# BLDC-FTDI.net
KiCad netlist of a schematic drawn in Altium Designer
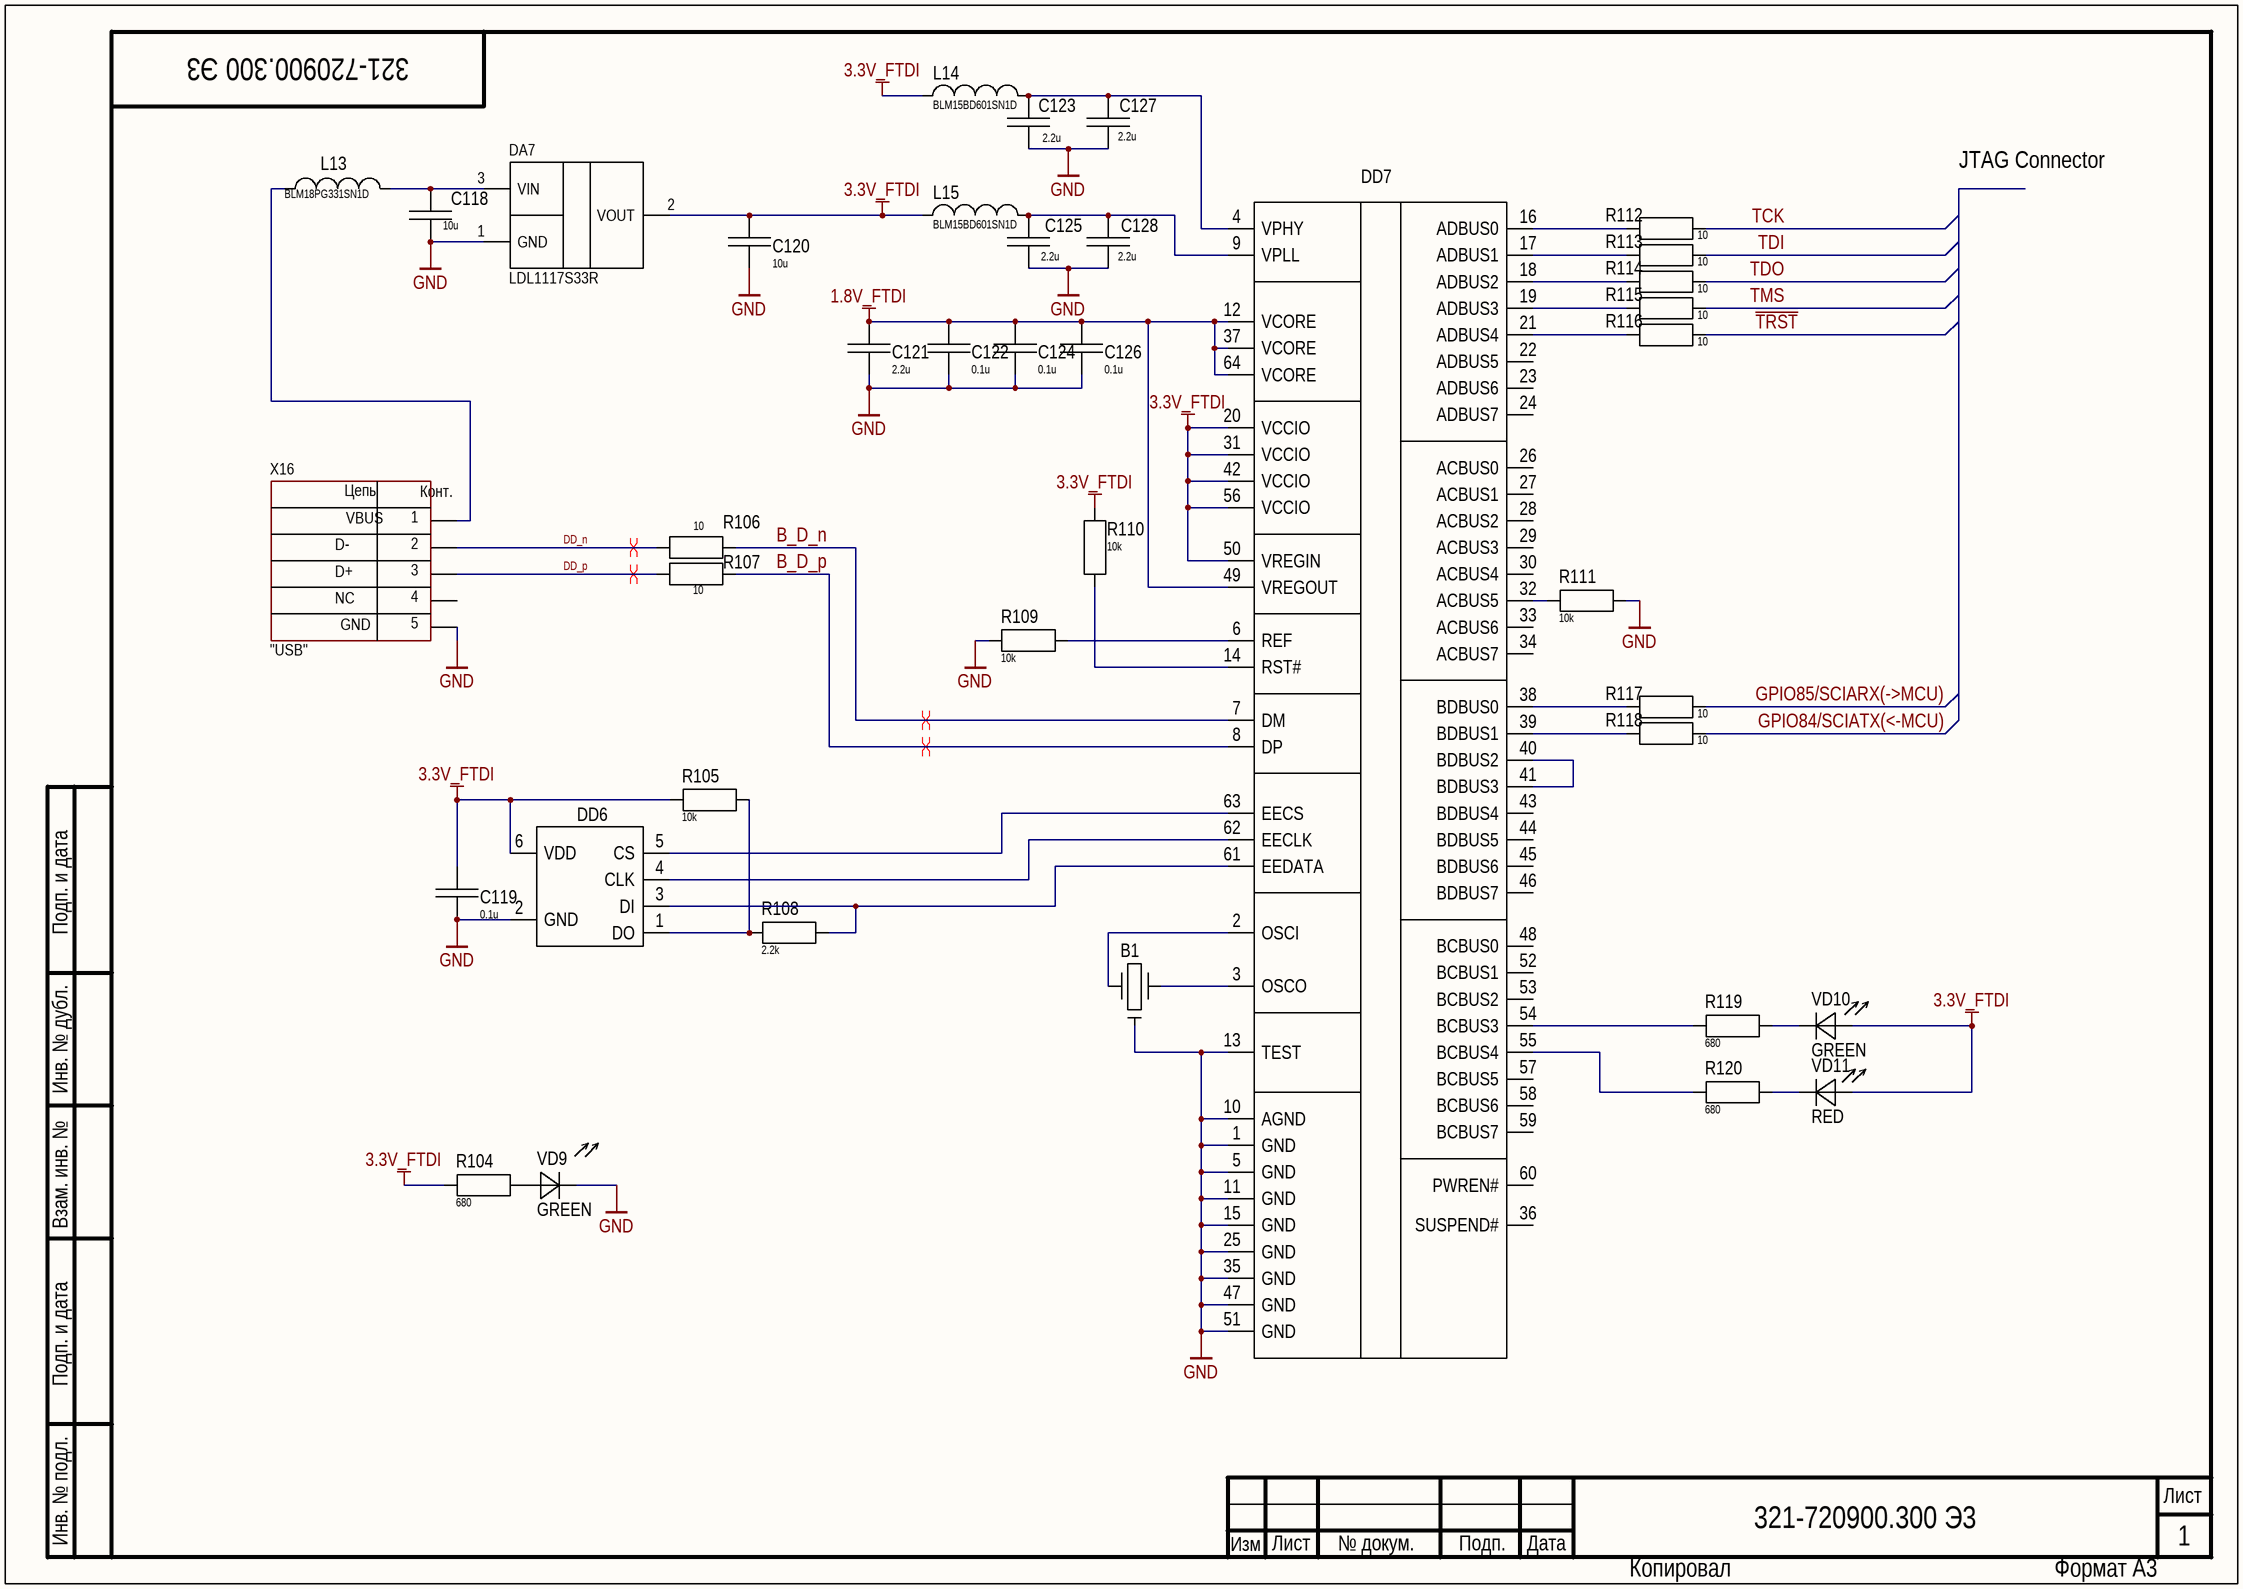
[diagram p0: BLDC-FTDI.SchDoc]

(export (version "E")
  (design (tool "Eeschema 10.0.6"))
  (components
    (comp (ref "B1")
      (value "CSTCE12M0G52-R0")
      (footprint "OSC: CSTCE")
      (libsource (lib "BKM_SCH_Lib") (part "CSTCE12M0G52-R0"))
    )
    (comp (ref "C118")
      (value "10u")
      (footprint "CAP: 0805")
      (fields (field (name "VOLTAGE") "6.3V") (field (name "PARTNUMBER") "CC0402MRX5R5BB106"))
      (libsource (lib "Fider_Board_Lib") (part "CAP 0805"))
    )
    (comp (ref "C119")
      (value "0.1u")
      (footprint "CAP: 0402")
      (fields
        (field (name "VOLTAGE") "10V")
        (field (name "PARTNUMBER") "C0402C104K8PAC")
        (field (name "MANUFACTURER") "Kemet")
      )
      (libsource (lib "Fider_Board_Lib") (part "CAP 0402"))
    )
    (comp (ref "C120")
      (value "10u")
      (footprint "CAP: 0805")
      (fields (field (name "VOLTAGE") "6.3V") (field (name "PARTNUMBER") "CC0402MRX5R5BB106"))
      (libsource (lib "Fider_Board_Lib") (part "CAP 0805"))
    )
    (comp (ref "C121")
      (value "2.2u")
      (footprint "CAP: 0402")
      (fields (field (name "VOLTAGE") "6.3V") (field (name "PARTNUMBER") "CC0402MRX5R5BB106"))
      (libsource (lib "Fider_Board_Lib") (part "CAP 0402"))
    )
    (comp (ref "C122")
      (value "0.1u")
      (footprint "CAP: 0402")
      (fields
        (field (name "VOLTAGE") "10V")
        (field (name "PARTNUMBER") "C0402C104K8PAC")
        (field (name "MANUFACTURER") "Kemet")
      )
      (libsource (lib "Fider_Board_Lib") (part "CAP 0402"))
    )
    (comp (ref "C123")
      (value "2.2u")
      (footprint "CAP: 0402")
      (fields (field (name "VOLTAGE") "6.3V") (field (name "PARTNUMBER") "CC0402MRX5R5BB106"))
      (libsource (lib "Fider_Board_Lib") (part "CAP 0402"))
    )
    (comp (ref "C124")
      (value "0.1u")
      (footprint "CAP: 0402")
      (fields
        (field (name "VOLTAGE") "10V")
        (field (name "PARTNUMBER") "C0402C104K8PAC")
        (field (name "MANUFACTURER") "Kemet")
      )
      (libsource (lib "Fider_Board_Lib") (part "CAP 0402"))
    )
    (comp (ref "C125")
      (value "2.2u")
      (footprint "CAP: 0402")
      (fields (field (name "VOLTAGE") "6.3V") (field (name "PARTNUMBER") "CC0402MRX5R5BB106"))
      (libsource (lib "Fider_Board_Lib") (part "CAP 0402"))
    )
    (comp (ref "C126")
      (value "0.1u")
      (footprint "CAP: 0402")
      (fields
        (field (name "VOLTAGE") "10V")
        (field (name "PARTNUMBER") "C0402C104K8PAC")
        (field (name "MANUFACTURER") "Kemet")
      )
      (libsource (lib "Fider_Board_Lib") (part "CAP 0402"))
    )
    (comp (ref "C127")
      (value "2.2u")
      (footprint "CAP: 0402")
      (fields (field (name "VOLTAGE") "6.3V") (field (name "PARTNUMBER") "CC0402MRX5R5BB106"))
      (libsource (lib "Fider_Board_Lib") (part "CAP 0402"))
    )
    (comp (ref "C128")
      (value "2.2u")
      (footprint "CAP: 0402")
      (fields (field (name "VOLTAGE") "6.3V") (field (name "PARTNUMBER") "CC0402MRX5R5BB106"))
      (libsource (lib "Fider_Board_Lib") (part "CAP 0402"))
    )
    (comp (ref "DA7")
      (value "~")
      (footprint "StandardCase:SOT223")
      (description "Linear voltage regulator")
      (fields
        (field (name "MANUFACTURER") "STMicroelectronics")
        (field (name "VALUEMANUFACTURERPARTNUMBER") "Linear voltage regulator, input 3.9...18V, 0.6V, output 3.3V, 1.2A, -40...+85°C, SOT223")
        (field (name "PARTNUMBER") "LDL1117S33R")
      )
      (libsource (lib "IC. Power supply") (part "LDL1117S33R"))
    )
    (comp (ref "DD6")
      (value "93LC56BT-I/OT")
      (footprint "SOT23-6")
      (libsource (lib "BKM_SCH_Lib") (part "93LC56BT-I/OT"))
    )
    (comp (ref "DD7")
      (value "FT2232HL")
      (footprint "64-LQFP")
      (libsource (lib "BKM_SCH_Lib") (part "FT2232HL"))
    )
    (comp (ref "L13")
      (value "BLM18PG331SN1D")
      (footprint "IND: 0603")
      (libsource (lib "Fider_Board_Lib") (part "BLM18PG331SN1D"))
    )
    (comp (ref "L14")
      (value "BLM15BD601SN1D")
      (footprint "IND: 0402")
      (libsource (lib "Fider_Board_Lib") (part "BLM15BD601SN1D"))
    )
    (comp (ref "L15")
      (value "BLM15BD601SN1D")
      (footprint "IND: 0402")
      (libsource (lib "Fider_Board_Lib") (part "BLM15BD601SN1D"))
    )
    (comp (ref "R104")
      (value "680")
      (footprint "RES: 0402")
      (fields (field (name "PARTNUMBER") "RC0402FR-07680RL"))
      (libsource (lib "Fider_Board_Lib") (part "RES 0402"))
    )
    (comp (ref "R105")
      (value "10k")
      (footprint "RES: 0402")
      (fields (field (name "PARTNUMBER") "RC0402FR-0710KL") (field (name "TOLERANCE") "1%"))
      (libsource (lib "Fider_Board_Lib") (part "RES 0402"))
    )
    (comp (ref "R106")
      (value "10")
      (footprint "RES: 0402")
      (fields (field (name "PARTNUMBER") "RC0402FR-0710RL") (field (name "TOLERANCE") "1%"))
      (libsource (lib "Fider_Board_Lib") (part "RES 0402"))
    )
    (comp (ref "R107")
      (value "10")
      (footprint "RES: 0402")
      (fields (field (name "PARTNUMBER") "RC0402FR-0710RL") (field (name "TOLERANCE") "1%"))
      (libsource (lib "Fider_Board_Lib") (part "RES 0402"))
    )
    (comp (ref "R108")
      (value "2.2k")
      (footprint "RES: 0402")
      (fields (field (name "PARTNUMBER") "RC0402FR-072K2L") (field (name "TOLERANCE") "1%"))
      (libsource (lib "Fider_Board_Lib") (part "RES 0402"))
    )
    (comp (ref "R109")
      (value "10k")
      (footprint "RES: 0402")
      (fields (field (name "PARTNUMBER") "RC0402FR-0710KL") (field (name "TOLERANCE") "1%"))
      (libsource (lib "Fider_Board_Lib") (part "RES 0402"))
    )
    (comp (ref "R110")
      (value "10k")
      (footprint "RES: 0402")
      (fields (field (name "PARTNUMBER") "RC0402FR-0710KL") (field (name "TOLERANCE") "1%"))
      (libsource (lib "Fider_Board_Lib") (part "RES 0402"))
    )
    (comp (ref "R111")
      (value "10k")
      (footprint "RES: 0402")
      (fields (field (name "PARTNUMBER") "RC0402FR-0710KL") (field (name "TOLERANCE") "1%"))
      (libsource (lib "Fider_Board_Lib") (part "RES 0402"))
    )
    (comp (ref "R112")
      (value "10")
      (footprint "RES: 0402")
      (fields (field (name "PARTNUMBER") "RC0402FR-0710RL") (field (name "TOLERANCE") "1%"))
      (libsource (lib "Fider_Board_Lib") (part "RES 0402"))
    )
    (comp (ref "R113")
      (value "10")
      (footprint "RES: 0402")
      (fields (field (name "PARTNUMBER") "RC0402FR-0710RL") (field (name "TOLERANCE") "1%"))
      (libsource (lib "Fider_Board_Lib") (part "RES 0402"))
    )
    (comp (ref "R114")
      (value "10")
      (footprint "RES: 0402")
      (fields (field (name "PARTNUMBER") "RC0402FR-0710RL") (field (name "TOLERANCE") "1%"))
      (libsource (lib "Fider_Board_Lib") (part "RES 0402"))
    )
    (comp (ref "R115")
      (value "10")
      (footprint "RES: 0402")
      (fields (field (name "PARTNUMBER") "RC0402FR-0710RL") (field (name "TOLERANCE") "1%"))
      (libsource (lib "Fider_Board_Lib") (part "RES 0402"))
    )
    (comp (ref "R116")
      (value "10")
      (footprint "RES: 0402")
      (fields (field (name "PARTNUMBER") "RC0402FR-0710RL") (field (name "TOLERANCE") "1%"))
      (libsource (lib "Fider_Board_Lib") (part "RES 0402"))
    )
    (comp (ref "R117")
      (value "10")
      (footprint "RES: 0402")
      (fields (field (name "PARTNUMBER") "RC0402FR-0710RL") (field (name "TOLERANCE") "1%"))
      (libsource (lib "Fider_Board_Lib") (part "RES 0402"))
    )
    (comp (ref "R118")
      (value "10")
      (footprint "RES: 0402")
      (fields (field (name "PARTNUMBER") "RC0402FR-0710RL") (field (name "TOLERANCE") "1%"))
      (libsource (lib "Fider_Board_Lib") (part "RES 0402"))
    )
    (comp (ref "R119")
      (value "680")
      (footprint "RES: 0402")
      (fields (field (name "PARTNUMBER") "RC0402FR-07680RL"))
      (libsource (lib "Fider_Board_Lib") (part "RES 0402"))
    )
    (comp (ref "R120")
      (value "680")
      (footprint "RES: 0402")
      (fields (field (name "PARTNUMBER") "RC0402FR-07680RL"))
      (libsource (lib "Fider_Board_Lib") (part "RES 0402"))
    )
    (comp (ref "VD9")
      (value "GREEN")
      (footprint "LED: 0402G")
      (fields (field (name "PARTNUMBER") "SML-P11MTT86R") (field (name "Comment") "Led 0402 GREEN"))
      (libsource (lib "Fider_Board_Lib") (part "Led 0402 GREEN"))
    )
    (comp (ref "VD10")
      (value "GREEN")
      (footprint "LED: 0402G")
      (fields (field (name "PARTNUMBER") "SML-P11MTT86R") (field (name "Comment") "Led 0402 GREEN"))
      (libsource (lib "Fider_Board_Lib") (part "Led 0402 GREEN"))
    )
    (comp (ref "VD11")
      (value "RED")
      (footprint "LED: 0402R")
      (fields (field (name "PARTNUMBER") "SML-P11VTT86R") (field (name "Comment") "Led 0402 RED"))
      (libsource (lib "Fider_Board_Lib") (part "Led 0402 RED"))
    )
    (comp (ref "X16")
      (value "~")
      (footprint "CustomCase:CON: 0675031020")
      (fields
        (field (name "MANUFACTURER") "Molex")
        (field (name "VALUEMANUFACTURERPARTNUMBER") "USB mini B")
        (field (name "PARTNUMBER") "0675031020")
        (field (name "COMMENTTEXT") "\"USB\"")
      )
      (libsource (lib "Connector") (part "Connector_USB_mini_B"))
    )
  )
  (nets
    (net (code "1") (name "/B_D_n") (class "Default")
      (node (ref "DD7") (pin "7") (pinfunction "DM_7") (pintype "passive"))
      (node (ref "R106") (pin "1") (pinfunction "1_1") (pintype "passive"))
    )
    (net (code "2") (name "/B_D_p") (class "Default")
      (node (ref "DD7") (pin "8") (pinfunction "DP_8") (pintype "passive"))
      (node (ref "R107") (pin "1") (pinfunction "1_1") (pintype "passive"))
    )
    (net (code "3") (name "/DD_n") (class "Default")
      (node (ref "R106") (pin "2") (pinfunction "2_2") (pintype "passive"))
      (node (ref "X16") (pin "2") (pinfunction "2_2") (pintype "passive"))
    )
    (net (code "4") (name "/DD_p") (class "Default")
      (node (ref "R107") (pin "2") (pinfunction "2_2") (pintype "passive"))
      (node (ref "X16") (pin "3") (pinfunction "3_3") (pintype "passive"))
    )
    (net (code "5") (name "/GPIO84{slash}SCIATX(<-MCU)") (class "Default")
      (node (ref "R118") (pin "1") (pinfunction "1_1") (pintype "passive"))
    )
    (net (code "6") (name "/GPIO85{slash}SCIARX(->MCU)") (class "Default")
      (node (ref "R117") (pin "1") (pinfunction "1_1") (pintype "passive"))
    )
    (net (code "7") (name "/TCK") (class "Default")
      (node (ref "R112") (pin "1") (pinfunction "1_1") (pintype "passive"))
    )
    (net (code "8") (name "/TDI") (class "Default")
      (node (ref "R113") (pin "1") (pinfunction "1_1") (pintype "passive"))
    )
    (net (code "9") (name "/TDO") (class "Default")
      (node (ref "R114") (pin "1") (pinfunction "1_1") (pintype "passive"))
    )
    (net (code "10") (name "/TMS") (class "Default")
      (node (ref "R115") (pin "1") (pinfunction "1_1") (pintype "passive"))
    )
    (net (code "11") (name "/~{TRST}") (class "Default")
      (node (ref "R116") (pin "1") (pinfunction "1_1") (pintype "passive"))
    )
    (net (code "12") (name "1.8V_FTDI") (class "Default")
      (node (ref "C121") (pin "2") (pinfunction "2_2") (pintype "passive"))
      (node (ref "C122") (pin "2") (pinfunction "2_2") (pintype "passive"))
      (node (ref "C124") (pin "2") (pinfunction "2_2") (pintype "passive"))
      (node (ref "C126") (pin "2") (pinfunction "2_2") (pintype "passive"))
      (node (ref "DD7") (pin "12") (pinfunction "VCORE_12") (pintype "passive"))
      (node (ref "DD7") (pin "37") (pinfunction "VCORE_37") (pintype "passive"))
      (node (ref "DD7") (pin "49") (pinfunction "VREGOUT_49") (pintype "passive"))
      (node (ref "DD7") (pin "64") (pinfunction "VCORE_64") (pintype "passive"))
    )
    (net (code "13") (name "3.3V_FTDI") (class "Default")
      (node (ref "C119") (pin "2") (pinfunction "2_2") (pintype "passive"))
      (node (ref "C120") (pin "2") (pinfunction "2_2") (pintype "passive"))
      (node (ref "DA7") (pin "2") (pinfunction "VOUT_2") (pintype "power_in"))
      (node (ref "DD6") (pin "6") (pinfunction "VDD_6") (pintype "passive"))
      (node (ref "DD7") (pin "20") (pinfunction "VCCIO_20") (pintype "passive"))
      (node (ref "DD7") (pin "31") (pinfunction "VCCIO_31") (pintype "passive"))
      (node (ref "DD7") (pin "42") (pinfunction "VCCIO_42") (pintype "passive"))
      (node (ref "DD7") (pin "50") (pinfunction "VREGIN_50") (pintype "passive"))
      (node (ref "DD7") (pin "56") (pinfunction "VCCIO_56") (pintype "passive"))
      (node (ref "L14") (pin "1") (pinfunction "1_1") (pintype "passive"))
      (node (ref "L15") (pin "1") (pinfunction "1_1") (pintype "passive"))
      (node (ref "R104") (pin "2") (pinfunction "2_2") (pintype "passive"))
      (node (ref "R105") (pin "2") (pinfunction "2_2") (pintype "passive"))
      (node (ref "R110") (pin "1") (pinfunction "1_1") (pintype "passive"))
      (node (ref "VD10") (pin "1") (pinfunction "1_1") (pintype "passive"))
      (node (ref "VD11") (pin "1") (pinfunction "1_1") (pintype "passive"))
    )
    (net (code "14") (name "GND") (class "Default")
      (node (ref "B1") (pin "2") (pintype "passive"))
      (node (ref "C118") (pin "1") (pinfunction "1_1") (pintype "passive"))
      (node (ref "C119") (pin "1") (pinfunction "1_1") (pintype "passive"))
      (node (ref "C120") (pin "1") (pinfunction "1_1") (pintype "passive"))
      (node (ref "C121") (pin "1") (pinfunction "1_1") (pintype "passive"))
      (node (ref "C122") (pin "1") (pinfunction "1_1") (pintype "passive"))
      (node (ref "C123") (pin "1") (pinfunction "1_1") (pintype "passive"))
      (node (ref "C124") (pin "1") (pinfunction "1_1") (pintype "passive"))
      (node (ref "C125") (pin "1") (pinfunction "1_1") (pintype "passive"))
      (node (ref "C126") (pin "1") (pinfunction "1_1") (pintype "passive"))
      (node (ref "C127") (pin "1") (pinfunction "1_1") (pintype "passive"))
      (node (ref "C128") (pin "1") (pinfunction "1_1") (pintype "passive"))
      (node (ref "DA7") (pin "1") (pinfunction "GND_1") (pintype "power_in"))
      (node (ref "DD6") (pin "2") (pinfunction "GND_2") (pintype "passive"))
      (node (ref "DD7") (pin "1") (pinfunction "GND_1") (pintype "passive"))
      (node (ref "DD7") (pin "10") (pinfunction "AGND_10") (pintype "passive"))
      (node (ref "DD7") (pin "11") (pinfunction "GND_11") (pintype "passive"))
      (node (ref "DD7") (pin "13") (pinfunction "TEST_13") (pintype "passive"))
      (node (ref "DD7") (pin "15") (pinfunction "GND_15") (pintype "passive"))
      (node (ref "DD7") (pin "25") (pinfunction "GND_25") (pintype "passive"))
      (node (ref "DD7") (pin "35") (pinfunction "GND_35") (pintype "passive"))
      (node (ref "DD7") (pin "47") (pinfunction "GND_47") (pintype "passive"))
      (node (ref "DD7") (pin "5") (pinfunction "GND_5") (pintype "passive"))
      (node (ref "DD7") (pin "51") (pinfunction "GND_51") (pintype "passive"))
      (node (ref "R109") (pin "2") (pinfunction "2_2") (pintype "passive"))
      (node (ref "R111") (pin "2") (pinfunction "2_2") (pintype "passive"))
      (node (ref "VD9") (pin "2") (pinfunction "2_2") (pintype "passive"))
      (node (ref "X16") (pin "5") (pinfunction "5_5") (pintype "passive"))
    )
    (net (code "15") (name "Net-(DA7-VIN)") (class "Default")
      (node (ref "C118") (pin "2") (pinfunction "2_2") (pintype "passive"))
      (node (ref "DA7") (pin "3") (pinfunction "VIN_3") (pintype "power_in"))
      (node (ref "L13") (pin "1") (pinfunction "1_1") (pintype "passive"))
    )
    (net (code "16") (name "Net-(DD6-CLK)") (class "Default")
      (node (ref "DD6") (pin "4") (pinfunction "CLK_4") (pintype "passive"))
      (node (ref "DD7") (pin "62") (pinfunction "EECLK_62") (pintype "passive"))
    )
    (net (code "17") (name "Net-(DD6-CS)") (class "Default")
      (node (ref "DD6") (pin "5") (pinfunction "CS_5") (pintype "passive"))
      (node (ref "DD7") (pin "63") (pinfunction "EECS_63") (pintype "passive"))
    )
    (net (code "18") (name "Net-(DD6-DI)") (class "Default")
      (node (ref "DD6") (pin "3") (pinfunction "DI_3") (pintype "passive"))
      (node (ref "DD7") (pin "61") (pinfunction "EEDATA_61") (pintype "passive"))
      (node (ref "R108") (pin "1") (pinfunction "1_1") (pintype "passive"))
    )
    (net (code "19") (name "Net-(DD6-DO)") (class "Default")
      (node (ref "DD6") (pin "1") (pinfunction "DO_1") (pintype "passive"))
      (node (ref "R105") (pin "1") (pinfunction "1_1") (pintype "passive"))
      (node (ref "R108") (pin "2") (pinfunction "2_2") (pintype "passive"))
    )
    (net (code "20") (name "Net-(DD7-ACBUS5)") (class "Default")
      (node (ref "DD7") (pin "32") (pinfunction "ACBUS5_32") (pintype "passive"))
      (node (ref "R111") (pin "1") (pinfunction "1_1") (pintype "passive"))
    )
    (net (code "21") (name "Net-(DD7-ADBUS0)") (class "Default")
      (node (ref "DD7") (pin "16") (pinfunction "ADBUS0_16") (pintype "passive"))
      (node (ref "R112") (pin "2") (pinfunction "2_2") (pintype "passive"))
    )
    (net (code "22") (name "Net-(DD7-ADBUS1)") (class "Default")
      (node (ref "DD7") (pin "17") (pinfunction "ADBUS1_17") (pintype "passive"))
      (node (ref "R113") (pin "2") (pinfunction "2_2") (pintype "passive"))
    )
    (net (code "23") (name "Net-(DD7-ADBUS2)") (class "Default")
      (node (ref "DD7") (pin "18") (pinfunction "ADBUS2_18") (pintype "passive"))
      (node (ref "R114") (pin "2") (pinfunction "2_2") (pintype "passive"))
    )
    (net (code "24") (name "Net-(DD7-ADBUS3)") (class "Default")
      (node (ref "DD7") (pin "19") (pinfunction "ADBUS3_19") (pintype "passive"))
      (node (ref "R115") (pin "2") (pinfunction "2_2") (pintype "passive"))
    )
    (net (code "25") (name "Net-(DD7-ADBUS4)") (class "Default")
      (node (ref "DD7") (pin "21") (pinfunction "ADBUS4_21") (pintype "passive"))
      (node (ref "R116") (pin "2") (pinfunction "2_2") (pintype "passive"))
    )
    (net (code "26") (name "Net-(DD7-BCBUS3)") (class "Default")
      (node (ref "DD7") (pin "54") (pinfunction "BCBUS3_54") (pintype "passive"))
      (node (ref "R119") (pin "1") (pinfunction "1_1") (pintype "passive"))
    )
    (net (code "27") (name "Net-(DD7-BCBUS4)") (class "Default")
      (node (ref "DD7") (pin "55") (pinfunction "BCBUS4_55") (pintype "passive"))
      (node (ref "R120") (pin "1") (pinfunction "1_1") (pintype "passive"))
    )
    (net (code "28") (name "Net-(DD7-BDBUS0)") (class "Default")
      (node (ref "DD7") (pin "38") (pinfunction "BDBUS0_38") (pintype "passive"))
      (node (ref "R117") (pin "2") (pinfunction "2_2") (pintype "passive"))
    )
    (net (code "29") (name "Net-(DD7-BDBUS1)") (class "Default")
      (node (ref "DD7") (pin "39") (pinfunction "BDBUS1_39") (pintype "passive"))
      (node (ref "R118") (pin "2") (pinfunction "2_2") (pintype "passive"))
    )
    (net (code "30") (name "Net-(DD7-BDBUS2)") (class "Default")
      (node (ref "DD7") (pin "40") (pinfunction "BDBUS2_40") (pintype "passive"))
      (node (ref "DD7") (pin "41") (pinfunction "BDBUS3_41") (pintype "passive"))
    )
    (net (code "31") (name "Net-(DD7-OSCI)") (class "Default")
      (node (ref "B1") (pin "1") (pintype "passive"))
      (node (ref "DD7") (pin "2") (pinfunction "OSCI_2") (pintype "passive"))
    )
    (net (code "32") (name "Net-(DD7-OSCO)") (class "Default")
      (node (ref "B1") (pin "3") (pintype "passive"))
      (node (ref "DD7") (pin "3") (pinfunction "OSCO_3") (pintype "passive"))
    )
    (net (code "33") (name "Net-(DD7-REF)") (class "Default")
      (node (ref "DD7") (pin "6") (pinfunction "REF_6") (pintype "passive"))
      (node (ref "R109") (pin "1") (pinfunction "1_1") (pintype "passive"))
    )
    (net (code "34") (name "Net-(DD7-RST#)") (class "Default")
      (node (ref "DD7") (pin "14") (pinfunction "RST#_14") (pintype "passive"))
      (node (ref "R110") (pin "2") (pinfunction "2_2") (pintype "passive"))
    )
    (net (code "35") (name "Net-(DD7-VPHY)") (class "Default")
      (node (ref "C123") (pin "2") (pinfunction "2_2") (pintype "passive"))
      (node (ref "C127") (pin "2") (pinfunction "2_2") (pintype "passive"))
      (node (ref "DD7") (pin "4") (pinfunction "VPHY_4") (pintype "passive"))
      (node (ref "L14") (pin "2") (pinfunction "2_2") (pintype "passive"))
    )
    (net (code "36") (name "Net-(DD7-VPLL)") (class "Default")
      (node (ref "C125") (pin "2") (pinfunction "2_2") (pintype "passive"))
      (node (ref "C128") (pin "2") (pinfunction "2_2") (pintype "passive"))
      (node (ref "DD7") (pin "9") (pinfunction "VPLL_9") (pintype "passive"))
      (node (ref "L15") (pin "2") (pinfunction "2_2") (pintype "passive"))
    )
    (net (code "37") (name "Net-(L13-Pad2)") (class "Default")
      (node (ref "L13") (pin "2") (pinfunction "2_2") (pintype "passive"))
      (node (ref "X16") (pin "1") (pintype "passive"))
    )
    (net (code "38") (name "Net-(R104-Pad1)") (class "Default")
      (node (ref "R104") (pin "1") (pinfunction "1_1") (pintype "passive"))
      (node (ref "VD9") (pin "1") (pinfunction "1_1") (pintype "passive"))
    )
    (net (code "39") (name "Net-(R119-Pad2)") (class "Default")
      (node (ref "R119") (pin "2") (pinfunction "2_2") (pintype "passive"))
      (node (ref "VD10") (pin "2") (pinfunction "2_2") (pintype "passive"))
    )
    (net (code "40") (name "Net-(R120-Pad2)") (class "Default")
      (node (ref "R120") (pin "2") (pinfunction "2_2") (pintype "passive"))
      (node (ref "VD11") (pin "2") (pinfunction "2_2") (pintype "passive"))
    )
    (net (code "41") (name "unconnected-(DD7-ACBUS0-Pad26)") (class "Default")
      (node (ref "DD7") (pin "26") (pinfunction "ACBUS0_26") (pintype "passive"))
    )
    (net (code "42") (name "unconnected-(DD7-ACBUS1-Pad27)") (class "Default")
      (node (ref "DD7") (pin "27") (pinfunction "ACBUS1_27") (pintype "passive"))
    )
    (net (code "43") (name "unconnected-(DD7-ACBUS2-Pad28)") (class "Default")
      (node (ref "DD7") (pin "28") (pinfunction "ACBUS2_28") (pintype "passive"))
    )
    (net (code "44") (name "unconnected-(DD7-ACBUS3-Pad29)") (class "Default")
      (node (ref "DD7") (pin "29") (pinfunction "ACBUS3_29") (pintype "passive"))
    )
    (net (code "45") (name "unconnected-(DD7-ACBUS4-Pad30)") (class "Default")
      (node (ref "DD7") (pin "30") (pinfunction "ACBUS4_30") (pintype "passive"))
    )
    (net (code "46") (name "unconnected-(DD7-ACBUS6-Pad33)") (class "Default")
      (node (ref "DD7") (pin "33") (pinfunction "ACBUS6_33") (pintype "passive"))
    )
    (net (code "47") (name "unconnected-(DD7-ACBUS7-Pad34)") (class "Default")
      (node (ref "DD7") (pin "34") (pinfunction "ACBUS7_34") (pintype "passive"))
    )
    (net (code "48") (name "unconnected-(DD7-ADBUS5-Pad22)") (class "Default")
      (node (ref "DD7") (pin "22") (pinfunction "ADBUS5_22") (pintype "passive"))
    )
    (net (code "49") (name "unconnected-(DD7-ADBUS6-Pad23)") (class "Default")
      (node (ref "DD7") (pin "23") (pinfunction "ADBUS6_23") (pintype "passive"))
    )
    (net (code "50") (name "unconnected-(DD7-ADBUS7-Pad24)") (class "Default")
      (node (ref "DD7") (pin "24") (pinfunction "ADBUS7_24") (pintype "passive"))
    )
    (net (code "51") (name "unconnected-(DD7-BCBUS0-Pad48)") (class "Default")
      (node (ref "DD7") (pin "48") (pinfunction "BCBUS0_48") (pintype "passive"))
    )
    (net (code "52") (name "unconnected-(DD7-BCBUS1-Pad52)") (class "Default")
      (node (ref "DD7") (pin "52") (pinfunction "BCBUS1_52") (pintype "passive"))
    )
    (net (code "53") (name "unconnected-(DD7-BCBUS2-Pad53)") (class "Default")
      (node (ref "DD7") (pin "53") (pinfunction "BCBUS2_53") (pintype "passive"))
    )
    (net (code "54") (name "unconnected-(DD7-BCBUS5-Pad57)") (class "Default")
      (node (ref "DD7") (pin "57") (pinfunction "BCBUS5_57") (pintype "passive"))
    )
    (net (code "55") (name "unconnected-(DD7-BCBUS6-Pad58)") (class "Default")
      (node (ref "DD7") (pin "58") (pinfunction "BCBUS6_58") (pintype "passive"))
    )
    (net (code "56") (name "unconnected-(DD7-BCBUS7-Pad59)") (class "Default")
      (node (ref "DD7") (pin "59") (pinfunction "BCBUS7_59") (pintype "passive"))
    )
    (net (code "57") (name "unconnected-(DD7-BDBUS4-Pad43)") (class "Default")
      (node (ref "DD7") (pin "43") (pinfunction "BDBUS4_43") (pintype "passive"))
    )
    (net (code "58") (name "unconnected-(DD7-BDBUS5-Pad44)") (class "Default")
      (node (ref "DD7") (pin "44") (pinfunction "BDBUS5_44") (pintype "passive"))
    )
    (net (code "59") (name "unconnected-(DD7-BDBUS6-Pad45)") (class "Default")
      (node (ref "DD7") (pin "45") (pinfunction "BDBUS6_45") (pintype "passive"))
    )
    (net (code "60") (name "unconnected-(DD7-BDBUS7-Pad46)") (class "Default")
      (node (ref "DD7") (pin "46") (pinfunction "BDBUS7_46") (pintype "passive"))
    )
    (net (code "61") (name "unconnected-(DD7-PWREN#-Pad60)") (class "Default")
      (node (ref "DD7") (pin "60") (pinfunction "PWREN#_60") (pintype "passive"))
    )
    (net (code "62") (name "unconnected-(DD7-SUSPEND#-Pad36)") (class "Default")
      (node (ref "DD7") (pin "36") (pinfunction "SUSPEND#_36") (pintype "passive"))
    )
    (net (code "63") (name "unconnected-(X16-Pad4)") (class "Default")
      (node (ref "X16") (pin "4") (pinfunction "4_4") (pintype "passive"))
    )
  )
)
